# EEZ_DIB_AUX_PS_r2B2.net
KiCad netlist of a schematic drawn in EAGLE
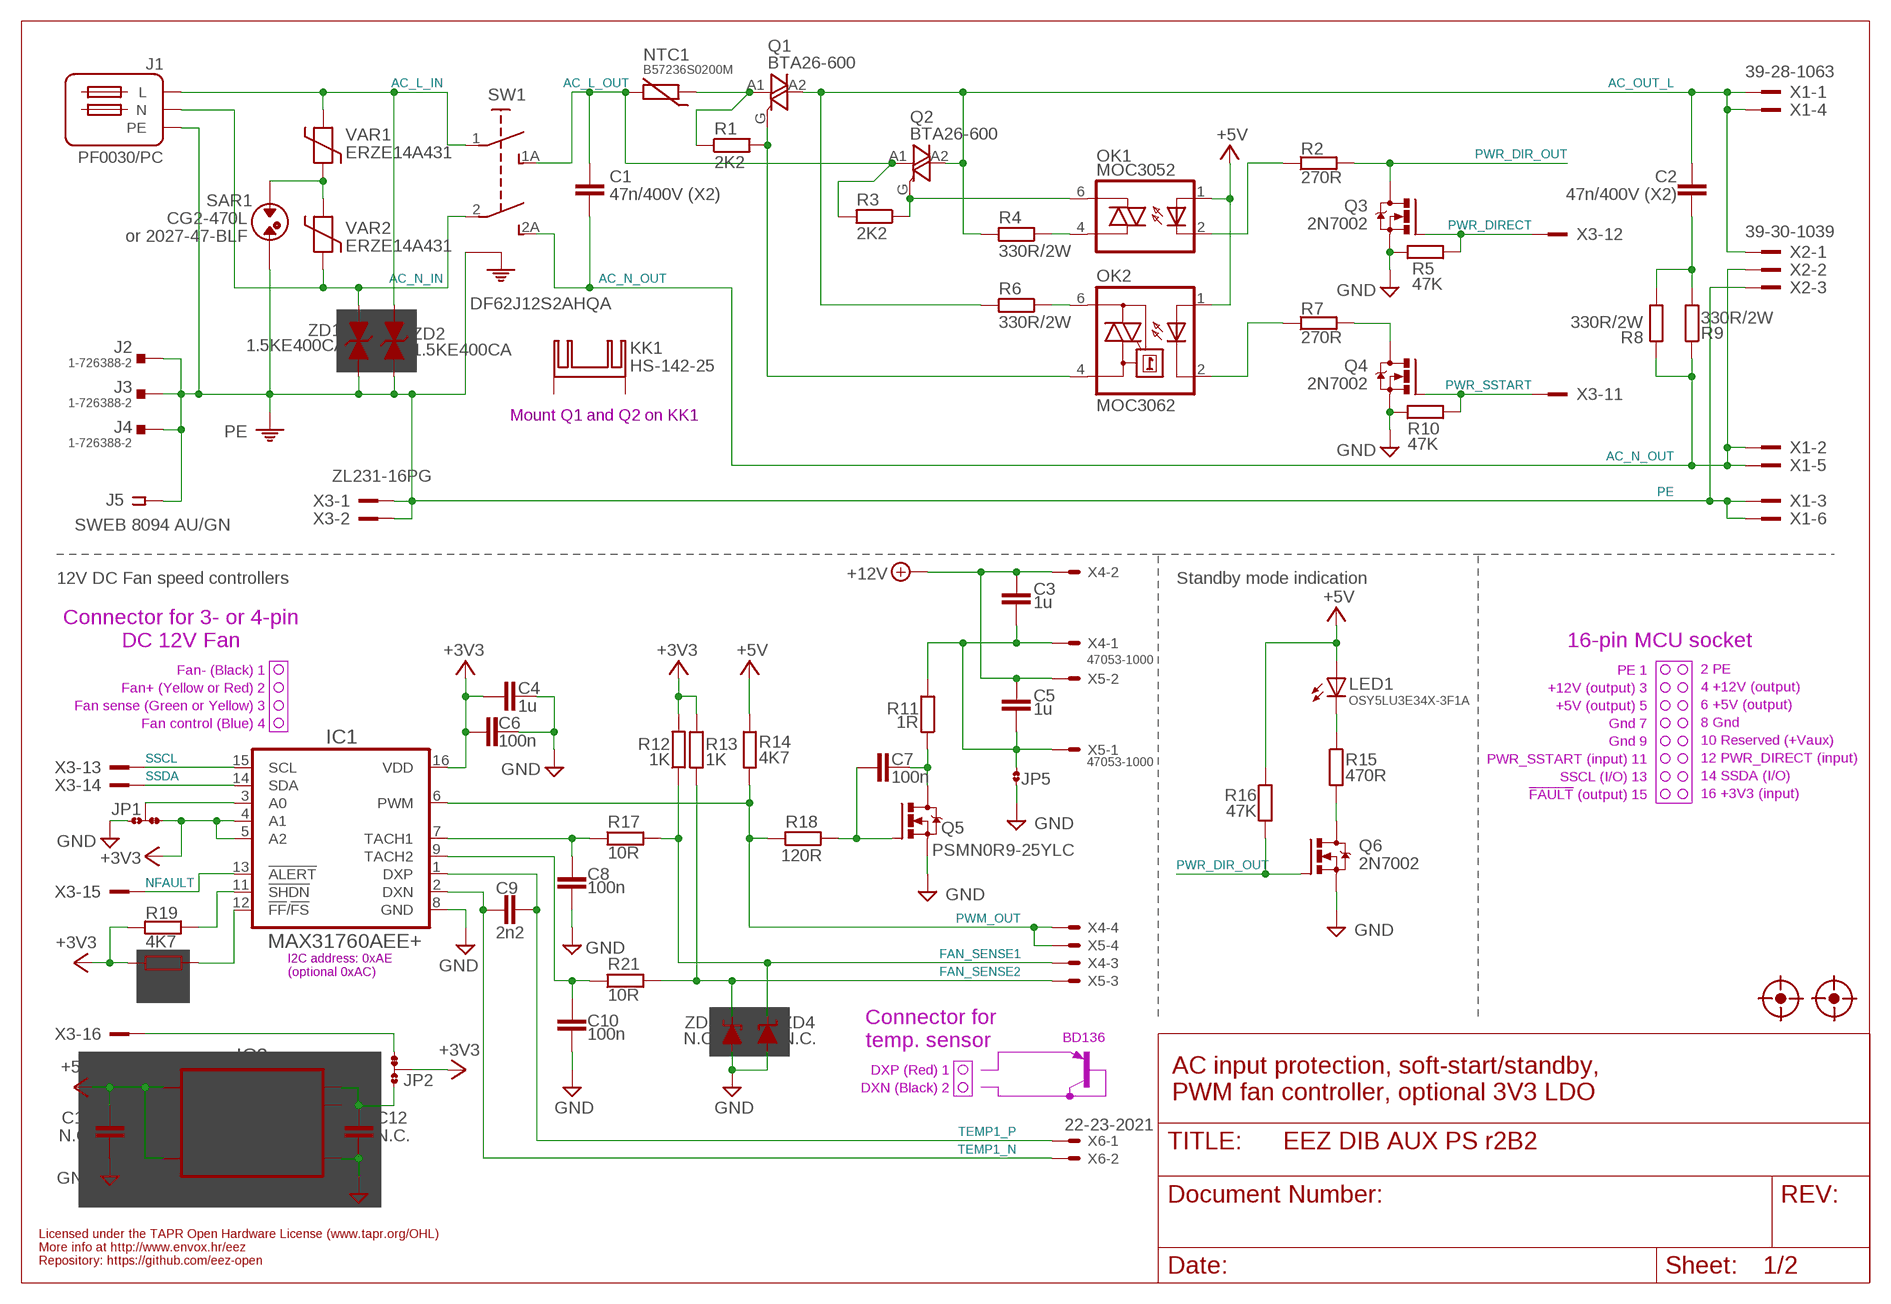
[diagram p0: schematic, sheet 1]
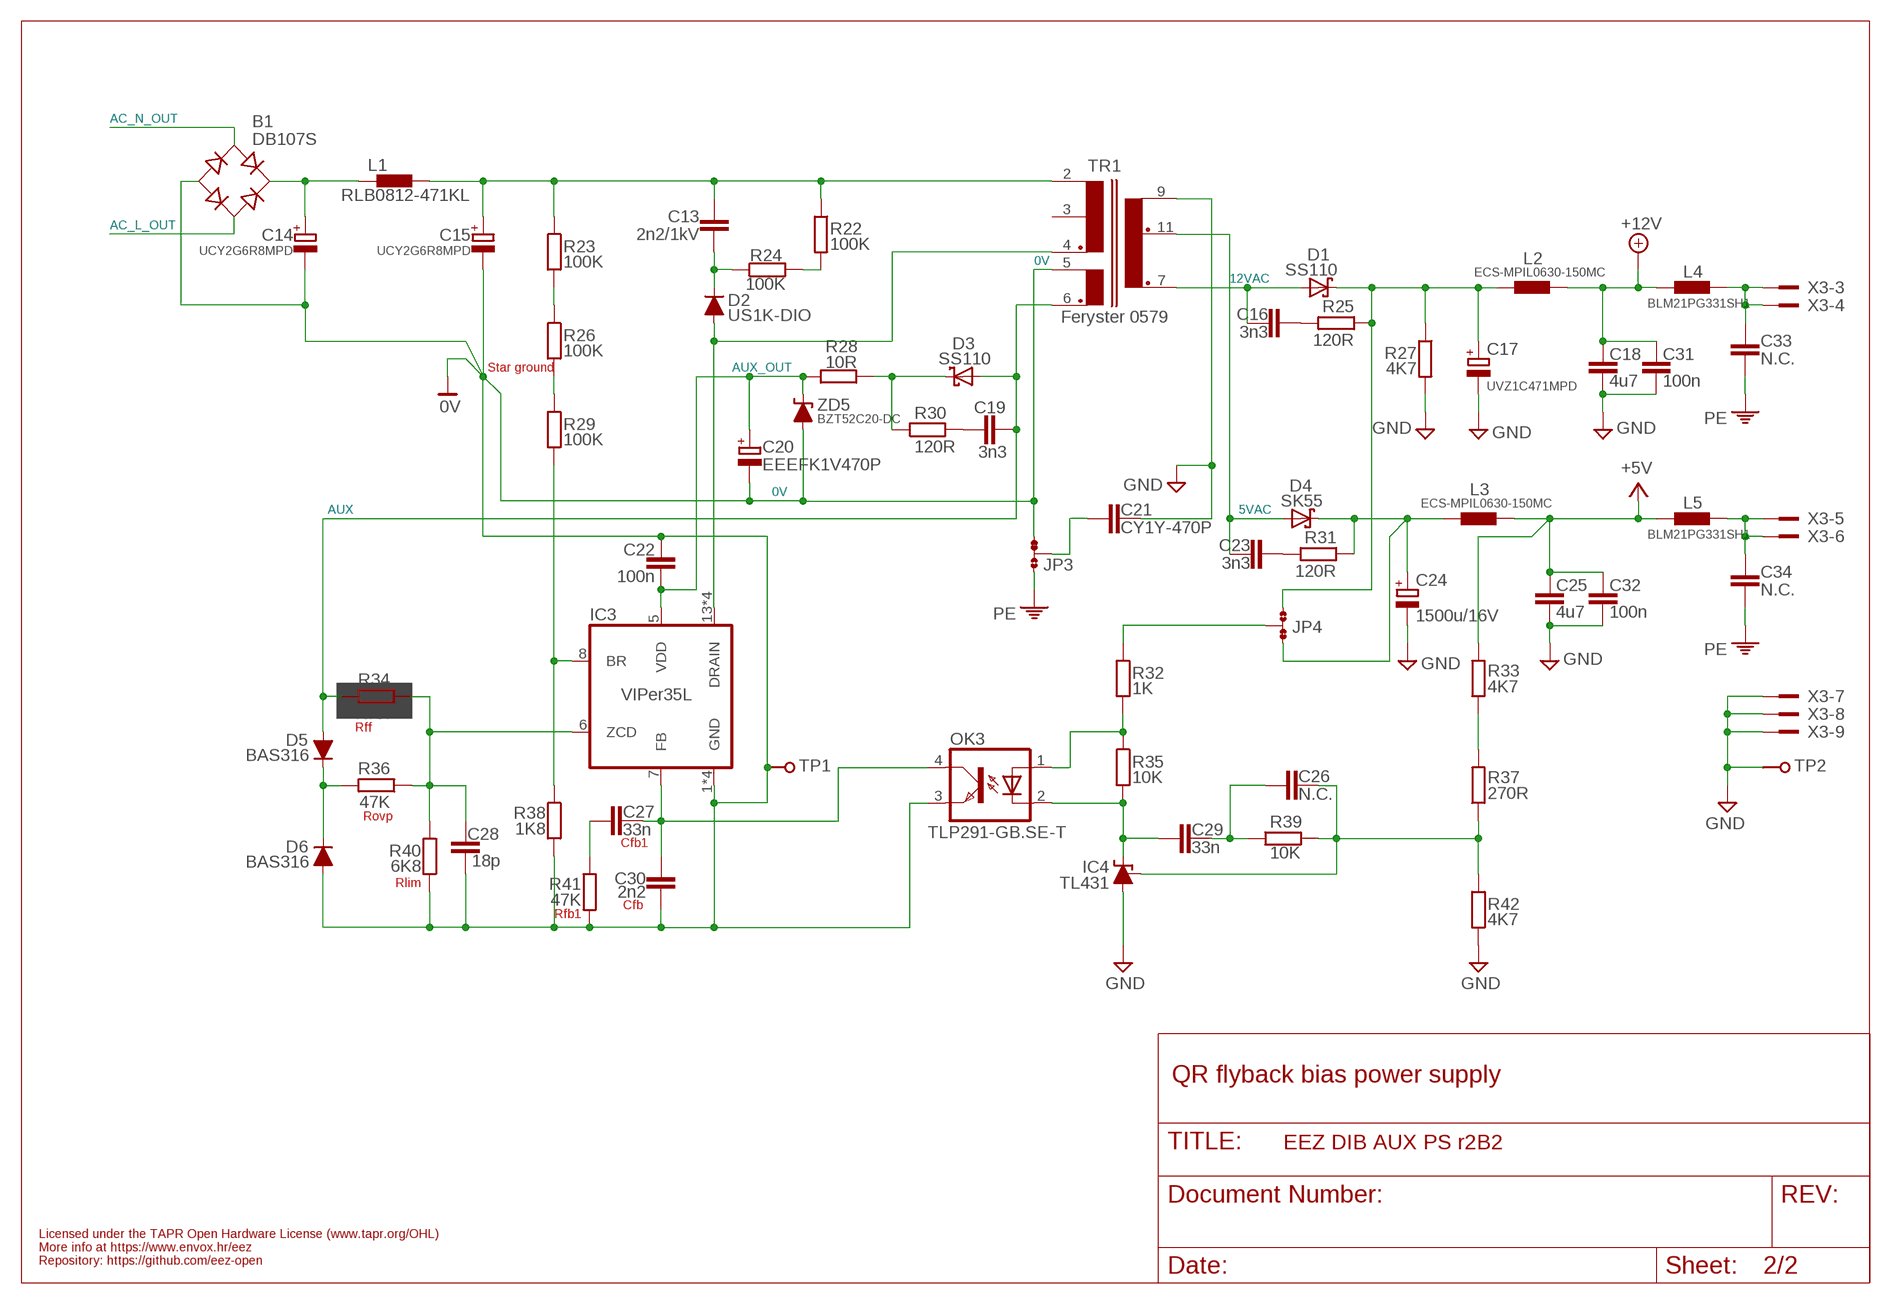
[diagram p1: schematic, sheet 2]

(export (version "E")
  (design (tool "Eeschema 10.0.6"))
  (components
    (comp (ref "C1")
      (value "47n/400V (X2)")
      (footprint "eagle-import:C102-054X133")
      (libsource (lib "eagle-import") (part "C-EU102-054X133"))
    )
    (comp (ref "C2")
      (value "47n/400V (X2)")
      (footprint "eagle-import:C102-054X133")
      (libsource (lib "eagle-import") (part "C-EU102-054X133"))
    )
    (comp (ref "C3")
      (value "1u")
      (footprint "eagle-import:C0805")
      (libsource (lib "eagle-import") (part "C-EUC0805"))
    )
    (comp (ref "C4")
      (value "1u")
      (footprint "eagle-import:C0805")
      (libsource (lib "eagle-import") (part "C-EUC0805"))
    )
    (comp (ref "C5")
      (value "1u")
      (footprint "eagle-import:C0805")
      (libsource (lib "eagle-import") (part "C-EUC0805"))
    )
    (comp (ref "C6")
      (value "100n")
      (footprint "eagle-import:C0603")
      (libsource (lib "eagle-import") (part "C-EUC0603"))
    )
    (comp (ref "C7")
      (value "100n")
      (footprint "eagle-import:C0805")
      (libsource (lib "eagle-import") (part "C-EUC0805"))
    )
    (comp (ref "C8")
      (value "100n")
      (footprint "eagle-import:C0603")
      (libsource (lib "eagle-import") (part "C-EUC0603"))
    )
    (comp (ref "C9")
      (value "2n2")
      (footprint "eagle-import:C0805")
      (libsource (lib "eagle-import") (part "C-EUC0805"))
    )
    (comp (ref "C10")
      (value "100n")
      (footprint "eagle-import:C0603")
      (libsource (lib "eagle-import") (part "C-EUC0603"))
    )
    (comp (ref "C11")
      (value "N.C.")
      (footprint "eagle-import:C0805")
      (libsource (lib "eagle-import") (part "C-EUC0805"))
    )
    (comp (ref "C12")
      (value "N.C.")
      (footprint "eagle-import:C0805")
      (libsource (lib "eagle-import") (part "C-EUC0805"))
    )
    (comp (ref "FM1")
      (value "FIDUCIAL")
      (footprint "eagle-import:FIDUCIAL")
      (libsource (lib "eagle-import") (part "FIDUCIAL"))
    )
    (comp (ref "FM2")
      (value "FIDUCIAL")
      (footprint "eagle-import:FIDUCIAL")
      (libsource (lib "eagle-import") (part "FIDUCIAL"))
    )
    (comp (ref "IC1")
      (value "MAX31760AEE+")
      (footprint "eagle-import:DBQ16")
      (libsource (lib "eagle-import") (part "MAX31760AEE+"))
    )
    (comp (ref "IC2")
      (value "LP2985")
      (footprint "eagle-import:SOT95P270X145-5N")
      (libsource (lib "eagle-import") (part "LP2985"))
    )
    (comp (ref "J1")
      (value "PF0030/PC")
      (footprint "eagle-import:PF0030_PC")
      (libsource (lib "eagle-import") (part "PF0030/PC"))
    )
    (comp (ref "J2")
      (value "1-726388-2")
      (footprint "eagle-import:PCB_TAB-4.8MM")
      (libsource (lib "eagle-import") (part "PCB_TAB4.8MM"))
    )
    (comp (ref "J3")
      (value "1-726388-2")
      (footprint "eagle-import:PCB_TAB-4.8MM")
      (libsource (lib "eagle-import") (part "PCB_TAB4.8MM"))
    )
    (comp (ref "J4")
      (value "1-726388-2")
      (footprint "eagle-import:PCB_TAB-4.8MM")
      (libsource (lib "eagle-import") (part "PCB_TAB4.8MM"))
    )
    (comp (ref "J5")
      (value "SWEB 8094 AU/GN")
      (footprint "eagle-import:S16N-PC")
      (libsource (lib "eagle-import") (part "BINDING_POSTCLIFF"))
    )
    (comp (ref "JP1")
      (value "JP3-CUT")
      (footprint "eagle-import:JP3-CUT")
      (libsource (lib "eagle-import") (part "JP3-CUT"))
    )
    (comp (ref "JP2")
      (value "JP3-CUT")
      (footprint "eagle-import:JP3-CUT")
      (libsource (lib "eagle-import") (part "JP3-CUT"))
    )
    (comp (ref "JP5")
      (value "JP2-CUT")
      (footprint "eagle-import:JP2-CUT")
      (libsource (lib "eagle-import") (part "JP2-CUT"))
    )
    (comp (ref "KK1")
      (value "HS-142-25")
      (footprint "eagle-import:SK129")
      (libsource (lib "eagle-import") (part "SK129-PAD"))
    )
    (comp (ref "LED1")
      (value "OSY5LU3E34X-3F1A")
      (footprint "eagle-import:OSG8")
      (libsource (lib "eagle-import") (part "LEDOSG8"))
    )
    (comp (ref "NTC1")
      (value "B57236S0200M")
      (footprint "eagle-import:NTC_11.5X6_RM5")
      (libsource (lib "eagle-import") (part "NTC11.5X6"))
    )
    (comp (ref "OK1")
      (value "MOC3052")
      (footprint "eagle-import:DIL6-SMD")
      (libsource (lib "eagle-import") (part "MOC305X"))
    )
    (comp (ref "OK2")
      (value "MOC3062")
      (footprint "eagle-import:DIL6-SMD")
      (fields
        (field (name "MF") "FAIRCHILD SEMICONDUCTOR")
        (field (name "MPN") "MOC3033S-M")
        (field (name "MF_1") "FAIRCHILD SEMICONDUCTOR")
        (field (name "MPN_1") "MOC3033S-M")
        (field (name "OC_FARNELL") "unknown")
        (field (name "OC_NEWARK") "05C2878")
      )
      (libsource (lib "eagle-import") (part "MOC30S33"))
    )
    (comp (ref "Q1")
      (value "BTA26-600")
      (footprint "eagle-import:TOP3S-1")
      (libsource (lib "eagle-import") (part "BTA26-V"))
    )
    (comp (ref "Q2")
      (value "BTA26-600")
      (footprint "eagle-import:TOP3S-1")
      (libsource (lib "eagle-import") (part "BTA26-V"))
    )
    (comp (ref "Q3")
      (value "2N7002")
      (footprint "eagle-import:SOT103P240X110-3N")
      (fields (field (name "MPN") "2N7002-7-F"))
      (libsource (lib "eagle-import") (part "2N7002"))
    )
    (comp (ref "Q4")
      (value "2N7002")
      (footprint "eagle-import:SOT103P240X110-3N")
      (fields (field (name "MPN") "2N7002-7-F"))
      (libsource (lib "eagle-import") (part "2N7002"))
    )
    (comp (ref "Q5")
      (value "PSMN0R9-25YLC")
      (footprint "eagle-import:SOT669")
      (libsource (lib "eagle-import") (part "N-MOSFETLFPAK"))
    )
    (comp (ref "Q6")
      (value "2N7002")
      (footprint "eagle-import:SOT103P240X110-3N")
      (fields
        (field (name "MPN") "2N7002-7-F")
        (field (name "MPN_1") "2N7002-7-F")
        (field (name "OC_FARNELL") "1713823")
        (field (name "OC_NEWARK") "25R5679")
        (field (name "PACKAGE") "SOT-23-3")
        (field (name "SUPPLIER") "DIODES INC.")
      )
      (libsource (lib "eagle-import") (part "2N7002"))
    )
    (comp (ref "R1")
      (value "2K2")
      (footprint "eagle-import:R0805")
      (libsource (lib "eagle-import") (part "R-EU_R0805"))
    )
    (comp (ref "R2")
      (value "270R")
      (footprint "eagle-import:R0805")
      (libsource (lib "eagle-import") (part "R-EU_R0805"))
    )
    (comp (ref "R3")
      (value "2K2")
      (footprint "eagle-import:R0805")
      (libsource (lib "eagle-import") (part "R-EU_R0805"))
    )
    (comp (ref "R4")
      (value "330R/2W")
      (footprint "eagle-import:R2512")
      (libsource (lib "eagle-import") (part "R-EU_R2512"))
    )
    (comp (ref "R5")
      (value "47K")
      (footprint "eagle-import:R0805")
      (libsource (lib "eagle-import") (part "R-EU_R0805"))
    )
    (comp (ref "R6")
      (value "330R/2W")
      (footprint "eagle-import:R2512")
      (libsource (lib "eagle-import") (part "R-EU_R2512"))
    )
    (comp (ref "R7")
      (value "270R")
      (footprint "eagle-import:R0805")
      (libsource (lib "eagle-import") (part "R-EU_R0805"))
    )
    (comp (ref "R8")
      (value "330R/2W")
      (footprint "eagle-import:R2512")
      (libsource (lib "eagle-import") (part "R-EU_R2512"))
    )
    (comp (ref "R9")
      (value "330R/2W")
      (footprint "eagle-import:R2512")
      (libsource (lib "eagle-import") (part "R-EU_R2512"))
    )
    (comp (ref "R10")
      (value "47K")
      (footprint "eagle-import:R0805")
      (libsource (lib "eagle-import") (part "R-EU_R0805"))
    )
    (comp (ref "R11")
      (value "1R")
      (footprint "eagle-import:R0805")
      (libsource (lib "eagle-import") (part "R-EU_R0805"))
    )
    (comp (ref "R12")
      (value "1K")
      (footprint "eagle-import:R0805")
      (libsource (lib "eagle-import") (part "R-EU_R0805"))
    )
    (comp (ref "R13")
      (value "1K")
      (footprint "eagle-import:R0805")
      (libsource (lib "eagle-import") (part "R-EU_R0805"))
    )
    (comp (ref "R14")
      (value "4K7")
      (footprint "eagle-import:R0805")
      (libsource (lib "eagle-import") (part "R-EU_R0805"))
    )
    (comp (ref "R15")
      (value "470R")
      (footprint "eagle-import:R0805")
      (libsource (lib "eagle-import") (part "R-EU_R0805"))
    )
    (comp (ref "R16")
      (value "47K")
      (footprint "eagle-import:R0805")
      (libsource (lib "eagle-import") (part "R-EU_R0805"))
    )
    (comp (ref "R17")
      (value "10R")
      (footprint "eagle-import:R0805")
      (libsource (lib "eagle-import") (part "R-EU_R0805"))
    )
    (comp (ref "R18")
      (value "120R")
      (footprint "eagle-import:R0805")
      (libsource (lib "eagle-import") (part "R-EU_R0805"))
    )
    (comp (ref "R19")
      (value "4K7")
      (footprint "eagle-import:R0805")
      (libsource (lib "eagle-import") (part "R-EU_R0805"))
    )
    (comp (ref "R20")
      (value "N.C.")
      (footprint "eagle-import:R0805")
      (libsource (lib "eagle-import") (part "R-EU_R0805"))
    )
    (comp (ref "R21")
      (value "10R")
      (footprint "eagle-import:R0805")
      (libsource (lib "eagle-import") (part "R-EU_R0805"))
    )
    (comp (ref "SAR1")
      (value "CG2-470L")
      (footprint "eagle-import:SAR")
      (libsource (lib "eagle-import") (part "SAR"))
    )
    (comp (ref "SW1")
      (value "DF62J12S2AHQA")
      (footprint "eagle-import:DF62J12S2")
      (libsource (lib "eagle-import") (part "DF62J12S2AHQA"))
    )
    (comp (ref "VAR1")
      (value "ERZE14A431")
      (footprint "eagle-import:VARISTOR_13MM")
      (libsource (lib "eagle-import") (part "VARISTOR-13"))
    )
    (comp (ref "VAR2")
      (value "ERZE14A431")
      (footprint "eagle-import:VARISTOR_13MM")
      (libsource (lib "eagle-import") (part "VARISTOR-13"))
    )
    (comp (ref "X1")
      (value "39-28-1063")
      (footprint "eagle-import:MINIFIT_5566-06A_CRE")
      (libsource (lib "eagle-import") (part "MINIFIT_5566-06A-CRE"))
    )
    (comp (ref "X2")
      (value "39-30-1039")
      (footprint "eagle-import:MINIFIT_39301039_CRE")
      (libsource (lib "eagle-import") (part "MINIFIT_39301039-CREEPAGE"))
    )
    (comp (ref "X3")
      (value "ZL231-16PG")
      (footprint "eagle-import:IDC-16PIN")
      (libsource (lib "eagle-import") (part "IDC-16PIN"))
    )
    (comp (ref "X4")
      (value "47053-1000")
      (footprint "eagle-import:47053-1000")
      (libsource (lib "eagle-import") (part "47053-1000"))
    )
    (comp (ref "X5")
      (value "47053-1000")
      (footprint "eagle-import:47053-1000")
      (libsource (lib "eagle-import") (part "47053-1000"))
    )
    (comp (ref "X6")
      (value "22-23-2021")
      (footprint "eagle-import:22-23-2021")
      (fields (field (name "MF") "MOLEX"))
      (libsource (lib "eagle-import") (part "22-23-2021"))
    )
    (comp (ref "ZD1")
      (value "1.5KE400CA")
      (footprint "eagle-import:DO201-BIDIR")
      (libsource (lib "eagle-import") (part "1.5KE-BIDIR"))
    )
    (comp (ref "ZD2")
      (value "1.5KE400CA")
      (footprint "eagle-import:DO201-BIDIR")
      (libsource (lib "eagle-import") (part "1.5KE-BIDIR"))
    )
    (comp (ref "ZD3")
      (value "N.C.")
      (footprint "eagle-import:SOD123")
      (libsource (lib "eagle-import") (part "ZENER-DIODESOD123"))
    )
    (comp (ref "ZD4")
      (value "N.C.")
      (footprint "eagle-import:SOD123")
      (libsource (lib "eagle-import") (part "ZENER-DIODESOD123"))
    )
    (comp (ref "B1")
      (value "DB107S")
      (footprint "eagle-import:DBS")
      (libsource (lib "eagle-import") (part "DB?GS107"))
    )
    (comp (ref "C13")
      (value "2n2/1kV")
      (footprint "eagle-import:C1210")
      (libsource (lib "eagle-import") (part "C-EUC1210"))
    )
    (comp (ref "C14")
      (value "UCY2G6R8MPD")
      (footprint "eagle-import:ECAP5_10.5")
      (libsource (lib "eagle-import") (part "ECAP5G_10.5MM"))
    )
    (comp (ref "C15")
      (value "UCY2G6R8MPD")
      (footprint "eagle-import:ECAP5_10.5")
      (libsource (lib "eagle-import") (part "ECAP5G_10.5MM"))
    )
    (comp (ref "C16")
      (value "3n3")
      (footprint "eagle-import:C0805")
      (libsource (lib "eagle-import") (part "C-EUC0805"))
    )
    (comp (ref "C17")
      (value "UVZ1C471MPD")
      (footprint "eagle-import:ECAP5_10.5")
      (libsource (lib "eagle-import") (part "ECAP5G_10.5MM"))
    )
    (comp (ref "C18")
      (value "4u7")
      (footprint "eagle-import:C1210")
      (libsource (lib "eagle-import") (part "C-EUC1210"))
    )
    (comp (ref "C19")
      (value "3n3")
      (footprint "eagle-import:C0805")
      (libsource (lib "eagle-import") (part "C-EUC0805"))
    )
    (comp (ref "C20")
      (value "EEEFK1V470P")
      (footprint "eagle-import:CAPAE660X610N")
      (libsource (lib "eagle-import") (part "ECAPPANASONIC_H"))
    )
    (comp (ref "C21")
      (value "CY1Y-470P")
      (footprint "eagle-import:CY075-032X103")
      (libsource (lib "eagle-import") (part "C-EUCY"))
    )
    (comp (ref "C22")
      (value "100n")
      (footprint "eagle-import:C0603")
      (libsource (lib "eagle-import") (part "C-EUC0603"))
    )
    (comp (ref "C23")
      (value "3n3")
      (footprint "eagle-import:C0805")
      (libsource (lib "eagle-import") (part "C-EUC0805"))
    )
    (comp (ref "C24")
      (value "1500u/16V")
      (footprint "eagle-import:ECAP5_13")
      (libsource (lib "eagle-import") (part "ECAP5G_13MM"))
    )
    (comp (ref "C25")
      (value "4u7")
      (footprint "eagle-import:C1210")
      (libsource (lib "eagle-import") (part "C-EUC1210"))
    )
    (comp (ref "C26")
      (value "N.C.")
      (footprint "eagle-import:C0805")
      (libsource (lib "eagle-import") (part "C-EUC0805"))
    )
    (comp (ref "C27")
      (value "33n")
      (footprint "eagle-import:C0805")
      (libsource (lib "eagle-import") (part "C-EUC0805"))
    )
    (comp (ref "C28")
      (value "18p")
      (footprint "eagle-import:C0603")
      (libsource (lib "eagle-import") (part "C-EUC0603"))
    )
    (comp (ref "C29")
      (value "33n")
      (footprint "eagle-import:C0805")
      (libsource (lib "eagle-import") (part "C-EUC0805"))
    )
    (comp (ref "C30")
      (value "2n2")
      (footprint "eagle-import:C0805")
      (libsource (lib "eagle-import") (part "C-EUC0805"))
    )
    (comp (ref "C31")
      (value "100n")
      (footprint "eagle-import:C0603")
      (libsource (lib "eagle-import") (part "C-EUC0603"))
    )
    (comp (ref "C32")
      (value "100n")
      (footprint "eagle-import:C0603")
      (libsource (lib "eagle-import") (part "C-EUC0603"))
    )
    (comp (ref "C33")
      (value "N.C.")
      (footprint "eagle-import:C1206")
      (libsource (lib "eagle-import") (part "C-EUC1206"))
    )
    (comp (ref "C34")
      (value "N.C.")
      (footprint "eagle-import:C1206")
      (libsource (lib "eagle-import") (part "C-EUC1206"))
    )
    (comp (ref "D1")
      (value "SS110")
      (footprint "eagle-import:SMB")
      (libsource (lib "eagle-import") (part "SCHOTTKYSMB"))
    )
    (comp (ref "D2")
      (value "US1K-DIO")
      (footprint "eagle-import:DO214AA")
      (libsource (lib "eagle-import") (part "DIODEDO214AA"))
    )
    (comp (ref "D3")
      (value "SS110")
      (footprint "eagle-import:SMB")
      (libsource (lib "eagle-import") (part "SCHOTTKYSMB"))
    )
    (comp (ref "D4")
      (value "SK55")
      (footprint "eagle-import:SMB")
      (libsource (lib "eagle-import") (part "SCHOTTKYSMB"))
    )
    (comp (ref "D5")
      (value "BAS316")
      (footprint "eagle-import:SOD323-R")
      (libsource (lib "eagle-import") (part "DIODESOD323R"))
    )
    (comp (ref "D6")
      (value "BAS316")
      (footprint "eagle-import:SOD323-R")
      (libsource (lib "eagle-import") (part "DIODESOD323R"))
    )
    (comp (ref "IC3")
      (value "VIPer35L")
      (footprint "eagle-import:SOIC-16")
      (libsource (lib "eagle-import") (part "VIPER35"))
    )
    (comp (ref "IC4")
      (value "TL431")
      (footprint "eagle-import:SOT103P240X110-3N")
      (libsource (lib "eagle-import") (part "TL431"))
    )
    (comp (ref "JP3")
      (value "JP3-CUT")
      (footprint "eagle-import:JP3-CUT")
      (libsource (lib "eagle-import") (part "JP3-CUT"))
    )
    (comp (ref "JP4")
      (value "JP3-CUT")
      (footprint "eagle-import:JP3-CUT")
      (libsource (lib "eagle-import") (part "JP3-CUT"))
    )
    (comp (ref "L1")
      (value "RLB0812-471KL")
      (footprint "eagle-import:FERSYTER_DSZ6")
      (libsource (lib "eagle-import") (part "FERYSTER_DSZ6"))
    )
    (comp (ref "L2")
      (value "ECS-MPIL0630-150MC")
      (footprint "eagle-import:DE0704")
      (libsource (lib "eagle-import") (part "DE0704"))
    )
    (comp (ref "L3")
      (value "ECS-MPIL0630-150MC")
      (footprint "eagle-import:DE0704")
      (libsource (lib "eagle-import") (part "DE0704"))
    )
    (comp (ref "L4")
      (value "BLM21PG331SH1")
      (footprint "eagle-import:0805")
      (libsource (lib "eagle-import") (part "L-EU0805"))
    )
    (comp (ref "L5")
      (value "BLM21PG331SH1")
      (footprint "eagle-import:0805")
      (libsource (lib "eagle-import") (part "L-EU0805"))
    )
    (comp (ref "OK3")
      (value "TLP291-GB.SE-T")
      (footprint "eagle-import:SO4")
      (libsource (lib "eagle-import") (part "TLP291"))
    )
    (comp (ref "R22")
      (value "100K")
      (footprint "eagle-import:R1206")
      (libsource (lib "eagle-import") (part "R-EU_R1206"))
    )
    (comp (ref "R23")
      (value "100K")
      (footprint "eagle-import:R1206")
      (libsource (lib "eagle-import") (part "R-EU_R1206"))
    )
    (comp (ref "R24")
      (value "100K")
      (footprint "eagle-import:R1206")
      (libsource (lib "eagle-import") (part "R-EU_R1206"))
    )
    (comp (ref "R25")
      (value "120R")
      (footprint "eagle-import:R0805")
      (libsource (lib "eagle-import") (part "R-EU_R0805"))
    )
    (comp (ref "R26")
      (value "100K")
      (footprint "eagle-import:R1206")
      (libsource (lib "eagle-import") (part "R-EU_R1206"))
    )
    (comp (ref "R27")
      (value "4K7")
      (footprint "eagle-import:R0805")
      (libsource (lib "eagle-import") (part "R-EU_R0805"))
    )
    (comp (ref "R28")
      (value "10R")
      (footprint "eagle-import:R0805")
      (libsource (lib "eagle-import") (part "R-EU_R0805"))
    )
    (comp (ref "R29")
      (value "100K")
      (footprint "eagle-import:R1206")
      (libsource (lib "eagle-import") (part "R-EU_R1206"))
    )
    (comp (ref "R30")
      (value "120R")
      (footprint "eagle-import:R0805")
      (libsource (lib "eagle-import") (part "R-EU_R0805"))
    )
    (comp (ref "R31")
      (value "120R")
      (footprint "eagle-import:R0805")
      (libsource (lib "eagle-import") (part "R-EU_R0805"))
    )
    (comp (ref "R32")
      (value "1K")
      (footprint "eagle-import:R0805")
      (libsource (lib "eagle-import") (part "R-EU_R0805"))
    )
    (comp (ref "R33")
      (value "4K7")
      (footprint "eagle-import:R0805")
      (libsource (lib "eagle-import") (part "R-EU_R0805"))
    )
    (comp (ref "R34")
      (value "N.C.")
      (footprint "eagle-import:R0805")
      (libsource (lib "eagle-import") (part "R-EU_R0805"))
    )
    (comp (ref "R35")
      (value "10K")
      (footprint "eagle-import:R0805")
      (libsource (lib "eagle-import") (part "R-EU_R0805"))
    )
    (comp (ref "R36")
      (value "47K")
      (footprint "eagle-import:R0805")
      (libsource (lib "eagle-import") (part "R-EU_R0805"))
    )
    (comp (ref "R37")
      (value "270R")
      (footprint "eagle-import:R0805")
      (libsource (lib "eagle-import") (part "R-EU_R0805"))
    )
    (comp (ref "R38")
      (value "1K8")
      (footprint "eagle-import:R0805")
      (libsource (lib "eagle-import") (part "R-EU_R0805"))
    )
    (comp (ref "R39")
      (value "10K")
      (footprint "eagle-import:R0805")
      (libsource (lib "eagle-import") (part "R-EU_R0805"))
    )
    (comp (ref "R40")
      (value "6K8")
      (footprint "eagle-import:R0805")
      (libsource (lib "eagle-import") (part "R-EU_R0805"))
    )
    (comp (ref "R41")
      (value "47K")
      (footprint "eagle-import:R0805")
      (libsource (lib "eagle-import") (part "R-EU_R0805"))
    )
    (comp (ref "R42")
      (value "4K7")
      (footprint "eagle-import:R0805")
      (libsource (lib "eagle-import") (part "R-EU_R0805"))
    )
    (comp (ref "TP1")
      (value "PCB_TEST_TABSHIELD")
      (footprint "eagle-import:PCB_SHIELD_TAB")
      (libsource (lib "eagle-import") (part "PCB_TEST_TABSHIELD"))
    )
    (comp (ref "TP2")
      (value "PCB_TEST_TABSHIELD")
      (footprint "eagle-import:PCB_SHIELD_TAB")
      (libsource (lib "eagle-import") (part "PCB_TEST_TABSHIELD"))
    )
    (comp (ref "TR1")
      (value "Feryster 0579")
      (footprint "eagle-import:FERYSTER_0579")
      (libsource (lib "eagle-import") (part "FERYSTER_0579"))
    )
    (comp (ref "ZD5")
      (value "BZT52C20-DC")
      (footprint "eagle-import:SOD123")
      (libsource (lib "eagle-import") (part "ZENER-DIODESOD123"))
    )
  )
  (nets
    (net (code "1") (name "+3V3") (class "Default")
      (node (ref "C4") (pin "2") (pinfunction "2_2") (pintype "passive"))
      (node (ref "C6") (pin "2") (pinfunction "2_2") (pintype "passive"))
      (node (ref "IC1") (pin "16") (pinfunction "VDD_16") (pintype "power_in"))
      (node (ref "IC1") (pin "4") (pinfunction "A1_4") (pintype "input"))
      (node (ref "IC1") (pin "5") (pinfunction "A2_5") (pintype "input"))
      (node (ref "JP1") (pin "NC") (pinfunction "NC_NC") (pintype "passive"))
      (node (ref "JP2") (pin "COM") (pinfunction "COM_COM") (pintype "passive"))
      (node (ref "R12") (pin "2") (pinfunction "2_2") (pintype "passive"))
      (node (ref "R13") (pin "2") (pinfunction "2_2") (pintype "passive"))
      (node (ref "R19") (pin "2") (pinfunction "2_2") (pintype "passive"))
      (node (ref "R20") (pin "2") (pinfunction "2_2") (pintype "passive"))
    )
    (net (code "2") (name "+5V") (class "Default")
      (node (ref "C11") (pin "1") (pinfunction "1_1") (pintype "passive"))
      (node (ref "C25") (pin "1") (pinfunction "1_1") (pintype "passive"))
      (node (ref "C32") (pin "1") (pinfunction "1_1") (pintype "passive"))
      (node (ref "IC2") (pin "1") (pinfunction "IN_1") (pintype "input"))
      (node (ref "IC2") (pin "3") (pinfunction "ON/~{OFF}_3") (pintype "input"))
      (node (ref "L3") (pin "2") (pinfunction "2_2") (pintype "passive"))
      (node (ref "L5") (pin "1") (pinfunction "1_1") (pintype "passive"))
      (node (ref "LED1") (pin "A") (pinfunction "A_A") (pintype "passive"))
      (node (ref "OK1") (pin "1") (pinfunction "A_1") (pintype "passive"))
      (node (ref "OK2") (pin "1") (pinfunction "A_1") (pintype "passive"))
      (node (ref "R14") (pin "1") (pinfunction "1_1") (pintype "passive"))
      (node (ref "R16") (pin "1") (pinfunction "1_1") (pintype "passive"))
      (node (ref "R33") (pin "2") (pinfunction "2_2") (pintype "passive"))
    )
    (net (code "3") (name "+12V") (class "Default")
      (node (ref "C18") (pin "1") (pinfunction "1_1") (pintype "passive"))
      (node (ref "C3") (pin "1") (pinfunction "1_1") (pintype "passive"))
      (node (ref "C31") (pin "1") (pinfunction "1_1") (pintype "passive"))
      (node (ref "C5") (pin "1") (pinfunction "1_1") (pintype "passive"))
      (node (ref "L2") (pin "2") (pinfunction "2_2") (pintype "passive"))
      (node (ref "L4") (pin "1") (pinfunction "1_1") (pintype "passive"))
      (node (ref "X4") (pin "2") (pinfunction "S_2") (pintype "passive"))
      (node (ref "X5") (pin "2") (pinfunction "S_2") (pintype "passive"))
    )
    (net (code "4") (name "0V") (class "Default")
      (node (ref "B1") (pin "-") (pinfunction "-_-") (pintype "passive"))
      (node (ref "C14") (pin "-") (pinfunction "-_-") (pintype "passive"))
      (node (ref "C15") (pin "-") (pinfunction "-_-") (pintype "passive"))
      (node (ref "C20") (pin "2") (pinfunction "-_2") (pintype "passive"))
      (node (ref "C22") (pin "1") (pinfunction "1_1") (pintype "passive"))
      (node (ref "C28") (pin "2") (pinfunction "2_2") (pintype "passive"))
      (node (ref "C30") (pin "2") (pinfunction "2_2") (pintype "passive"))
      (node (ref "D6") (pin "A") (pinfunction "A_A") (pintype "passive"))
      (node (ref "IC3") (pin "1") (pinfunction "GND_1") (pintype "passive"))
      (node (ref "IC3") (pin "2") (pinfunction "GND_2") (pintype "passive"))
      (node (ref "IC3") (pin "3") (pinfunction "GND_3") (pintype "passive"))
      (node (ref "IC3") (pin "4") (pinfunction "GND_4") (pintype "passive"))
      (node (ref "JP3") (pin "NC") (pinfunction "NC_NC") (pintype "passive"))
      (node (ref "OK3") (pin "3") (pinfunction "EMIT_3") (pintype "passive"))
      (node (ref "R38") (pin "2") (pinfunction "2_2") (pintype "passive"))
      (node (ref "R40") (pin "1") (pinfunction "1_1") (pintype "passive"))
      (node (ref "R41") (pin "2") (pinfunction "2_2") (pintype "passive"))
      (node (ref "TP1") (pin "1") (pinfunction "P$1_1") (pintype "bidirectional"))
      (node (ref "TR1") (pin "5") (pinfunction "AUX_5") (pintype "passive"))
      (node (ref "ZD5") (pin "A") (pinfunction "A_A") (pintype "passive"))
    )
    (net (code "5") (name "5VAC") (class "Default")
      (node (ref "C23") (pin "2") (pinfunction "2_2") (pintype "passive"))
      (node (ref "D4") (pin "A") (pinfunction "A_A") (pintype "passive"))
      (node (ref "TR1") (pin "11") (pinfunction "S1_DOT_11") (pintype "passive"))
    )
    (net (code "6") (name "12VAC") (class "Default")
      (node (ref "C16") (pin "2") (pinfunction "2_2") (pintype "passive"))
      (node (ref "D1") (pin "A") (pinfunction "A_A") (pintype "passive"))
      (node (ref "TR1") (pin "7") (pinfunction "S2_DOT_7") (pintype "passive"))
    )
    (net (code "7") (name "AC_L_IN") (class "Default")
      (node (ref "J1") (pin "L") (pinfunction "L_L") (pintype "bidirectional"))
      (node (ref "SW1") (pin "1") (pinfunction "P_1") (pintype "passive"))
      (node (ref "VAR1") (pin "2") (pinfunction "P$2_2") (pintype "bidirectional"))
      (node (ref "ZD2") (pin "A") (pinfunction "2_A") (pintype "passive"))
    )
    (net (code "8") (name "AC_L_OUT") (class "Default")
      (node (ref "B1") (pin "AC2") (pinfunction "AC2_AC2") (pintype "passive"))
      (node (ref "C1") (pin "1") (pinfunction "1_1") (pintype "passive"))
      (node (ref "NTC1") (pin "1") (pinfunction "P$1_1") (pintype "bidirectional"))
      (node (ref "Q2") (pin "A1") (pinfunction "A1_A1") (pintype "passive"))
      (node (ref "R3") (pin "2") (pinfunction "2_2") (pintype "passive"))
      (node (ref "SW1") (pin "1A") (pinfunction "S_1A") (pintype "passive"))
    )
    (net (code "9") (name "AC_N_IN") (class "Default")
      (node (ref "J1") (pin "N") (pinfunction "N_N") (pintype "bidirectional"))
      (node (ref "SW1") (pin "2") (pinfunction "P1_2") (pintype "passive"))
      (node (ref "VAR2") (pin "1") (pinfunction "P$1_1") (pintype "bidirectional"))
      (node (ref "ZD1") (pin "A") (pinfunction "2_A") (pintype "passive"))
    )
    (net (code "10") (name "AC_N_OUT") (class "Default")
      (node (ref "B1") (pin "AC1") (pinfunction "AC1_AC1") (pintype "passive"))
      (node (ref "C1") (pin "2") (pinfunction "2_2") (pintype "passive"))
      (node (ref "R8") (pin "1") (pinfunction "1_1") (pintype "passive"))
      (node (ref "R9") (pin "1") (pinfunction "1_1") (pintype "passive"))
      (node (ref "SW1") (pin "2A") (pinfunction "S1_2A") (pintype "passive"))
      (node (ref "X1") (pin "2") (pinfunction "1_2") (pintype "passive"))
      (node (ref "X1") (pin "5") (pinfunction "1_5") (pintype "passive"))
      (node (ref "X2") (pin "2") (pinfunction "1_2") (pintype "passive"))
    )
    (net (code "11") (name "AC_OUT_L") (class "Default")
      (node (ref "C2") (pin "1") (pinfunction "1_1") (pintype "passive"))
      (node (ref "Q1") (pin "A2") (pinfunction "A2_A2") (pintype "passive"))
      (node (ref "Q2") (pin "A2") (pinfunction "A2_A2") (pintype "passive"))
      (node (ref "R4") (pin "2") (pinfunction "2_2") (pintype "passive"))
      (node (ref "R6") (pin "2") (pinfunction "2_2") (pintype "passive"))
      (node (ref "X1") (pin "1") (pinfunction "1_1") (pintype "passive"))
      (node (ref "X1") (pin "4") (pinfunction "1_4") (pintype "passive"))
      (node (ref "X2") (pin "1") (pinfunction "1_1") (pintype "passive"))
    )
    (net (code "12") (name "AUX") (class "Default")
      (node (ref "C19") (pin "2") (pinfunction "2_2") (pintype "passive"))
      (node (ref "D3") (pin "A") (pinfunction "A_A") (pintype "passive"))
      (node (ref "D5") (pin "A") (pinfunction "A_A") (pintype "passive"))
      (node (ref "R34") (pin "2") (pinfunction "2_2") (pintype "passive"))
      (node (ref "TR1") (pin "6") (pinfunction "AUX_DOT_6") (pintype "passive"))
    )
    (net (code "13") (name "AUX_OUT") (class "Default")
      (node (ref "C20") (pin "1") (pinfunction "+_1") (pintype "passive"))
      (node (ref "C22") (pin "2") (pinfunction "2_2") (pintype "passive"))
      (node (ref "IC3") (pin "5") (pinfunction "VDD_5") (pintype "power_in"))
      (node (ref "R28") (pin "2") (pinfunction "2_2") (pintype "passive"))
      (node (ref "ZD5") (pin "C") (pinfunction "C_C") (pintype "passive"))
    )
    (net (code "14") (name "FAN_SENSE1") (class "Default")
      (node (ref "R12") (pin "1") (pinfunction "1_1") (pintype "passive"))
      (node (ref "R17") (pin "2") (pinfunction "2_2") (pintype "passive"))
      (node (ref "X4") (pin "3") (pinfunction "S_3") (pintype "passive"))
      (node (ref "ZD4") (pin "C") (pinfunction "C_C") (pintype "passive"))
    )
    (net (code "15") (name "FAN_SENSE2") (class "Default")
      (node (ref "R13") (pin "1") (pinfunction "1_1") (pintype "passive"))
      (node (ref "R21") (pin "2") (pinfunction "2_2") (pintype "passive"))
      (node (ref "X5") (pin "3") (pinfunction "S_3") (pintype "passive"))
      (node (ref "ZD3") (pin "C") (pinfunction "C_C") (pintype "passive"))
    )
    (net (code "16") (name "GND") (class "Default")
      (node (ref "C10") (pin "2") (pinfunction "2_2") (pintype "passive"))
      (node (ref "C11") (pin "2") (pinfunction "2_2") (pintype "passive"))
      (node (ref "C12") (pin "2") (pinfunction "2_2") (pintype "passive"))
      (node (ref "C17") (pin "-") (pinfunction "-_-") (pintype "passive"))
      (node (ref "C18") (pin "2") (pinfunction "2_2") (pintype "passive"))
      (node (ref "C21") (pin "2") (pinfunction "2_2") (pintype "passive"))
      (node (ref "C24") (pin "-") (pinfunction "-_-") (pintype "passive"))
      (node (ref "C25") (pin "2") (pinfunction "2_2") (pintype "passive"))
      (node (ref "C31") (pin "2") (pinfunction "2_2") (pintype "passive"))
      (node (ref "C32") (pin "2") (pinfunction "2_2") (pintype "passive"))
      (node (ref "C4") (pin "1") (pinfunction "1_1") (pintype "passive"))
      (node (ref "C6") (pin "1") (pinfunction "1_1") (pintype "passive"))
      (node (ref "C8") (pin "2") (pinfunction "2_2") (pintype "passive"))
      (node (ref "IC1") (pin "8") (pinfunction "GND_8") (pintype "power_in"))
      (node (ref "IC2") (pin "2") (pinfunction "GND_2") (pintype "passive"))
      (node (ref "IC4") (pin "3") (pinfunction "A_3") (pintype "passive"))
      (node (ref "JP1") (pin "NO") (pinfunction "NO_NO") (pintype "passive"))
      (node (ref "JP5") (pin "1") (pinfunction "1_1") (pintype "passive"))
      (node (ref "Q3") (pin "2") (pinfunction "S_2") (pintype "passive"))
      (node (ref "Q4") (pin "2") (pinfunction "S_2") (pintype "passive"))
      (node (ref "Q5") (pin "1") (pinfunction "S_1") (pintype "passive"))
      (node (ref "Q5") (pin "2") (pinfunction "S_2") (pintype "passive"))
      (node (ref "Q5") (pin "3") (pinfunction "S_3") (pintype "passive"))
      (node (ref "Q6") (pin "2") (pinfunction "S_2") (pintype "passive"))
      (node (ref "R10") (pin "1") (pinfunction "1_1") (pintype "passive"))
      (node (ref "R27") (pin "2") (pinfunction "2_2") (pintype "passive"))
      (node (ref "R42") (pin "1") (pinfunction "1_1") (pintype "passive"))
      (node (ref "R5") (pin "1") (pinfunction "1_1") (pintype "passive"))
      (node (ref "TP2") (pin "1") (pinfunction "P$1_1") (pintype "bidirectional"))
      (node (ref "TR1") (pin "9") (pinfunction "S_COMM_9") (pintype "passive"))
      (node (ref "X3") (pin "7") (pinfunction "1_7") (pintype "passive"))
      (node (ref "X3") (pin "8") (pinfunction "1_8") (pintype "passive"))
      (node (ref "X3") (pin "9") (pinfunction "1_9") (pintype "passive"))
      (node (ref "ZD3") (pin "A") (pinfunction "A_A") (pintype "passive"))
      (node (ref "ZD4") (pin "A") (pinfunction "A_A") (pintype "passive"))
    )
    (net (code "17") (name "NFAULT") (class "Default")
      (node (ref "IC1") (pin "13") (pinfunction "~{ALERT}_13") (pintype "output"))
      (node (ref "X3") (pin "15") (pinfunction "1_15") (pintype "passive"))
    )
    (net (code "18") (name "Net-(C2-Pad2)") (class "Default")
      (node (ref "C2") (pin "2") (pinfunction "2_2") (pintype "passive"))
      (node (ref "R8") (pin "2") (pinfunction "2_2") (pintype "passive"))
      (node (ref "R9") (pin "2") (pinfunction "2_2") (pintype "passive"))
    )
    (net (code "19") (name "Net-(C13-Pad2)") (class "Default")
      (node (ref "C13") (pin "2") (pinfunction "2_2") (pintype "passive"))
      (node (ref "D2") (pin "C") (pinfunction "C_C") (pintype "passive"))
      (node (ref "R24") (pin "1") (pinfunction "1_1") (pintype "passive"))
    )
    (net (code "20") (name "Net-(C16-Pad1)") (class "Default")
      (node (ref "C16") (pin "1") (pinfunction "1_1") (pintype "passive"))
      (node (ref "R25") (pin "2") (pinfunction "2_2") (pintype "passive"))
    )
    (net (code "21") (name "Net-(C17-Pad+)") (class "Default")
      (node (ref "C17") (pin "+") (pinfunction "+_+") (pintype "passive"))
      (node (ref "D1") (pin "C") (pinfunction "C_C") (pintype "passive"))
      (node (ref "JP4") (pin "NO") (pinfunction "NO_NO") (pintype "passive"))
      (node (ref "L2") (pin "1") (pinfunction "1_1") (pintype "passive"))
      (node (ref "R25") (pin "1") (pinfunction "1_1") (pintype "passive"))
      (node (ref "R27") (pin "1") (pinfunction "1_1") (pintype "passive"))
    )
    (net (code "22") (name "Net-(C19-Pad1)") (class "Default")
      (node (ref "C19") (pin "1") (pinfunction "1_1") (pintype "passive"))
      (node (ref "R30") (pin "2") (pinfunction "2_2") (pintype "passive"))
    )
    (net (code "23") (name "Net-(C21-Pad1)") (class "Default")
      (node (ref "C21") (pin "1") (pinfunction "1_1") (pintype "passive"))
      (node (ref "JP3") (pin "COM") (pinfunction "COM_COM") (pintype "passive"))
    )
    (net (code "24") (name "Net-(C23-Pad1)") (class "Default")
      (node (ref "C23") (pin "1") (pinfunction "1_1") (pintype "passive"))
      (node (ref "R31") (pin "2") (pinfunction "2_2") (pintype "passive"))
    )
    (net (code "25") (name "Net-(C24-Pad+)") (class "Default")
      (node (ref "C24") (pin "+") (pinfunction "+_+") (pintype "passive"))
      (node (ref "D4") (pin "C") (pinfunction "C_C") (pintype "passive"))
      (node (ref "JP4") (pin "NC") (pinfunction "NC_NC") (pintype "passive"))
      (node (ref "L3") (pin "1") (pinfunction "1_1") (pintype "passive"))
      (node (ref "R31") (pin "1") (pinfunction "1_1") (pintype "passive"))
    )
    (net (code "26") (name "Net-(C26-Pad1)") (class "Default")
      (node (ref "C26") (pin "1") (pinfunction "1_1") (pintype "passive"))
      (node (ref "C29") (pin "2") (pinfunction "2_2") (pintype "passive"))
      (node (ref "R39") (pin "1") (pinfunction "1_1") (pintype "passive"))
    )
    (net (code "27") (name "Net-(C27-Pad1)") (class "Default")
      (node (ref "C27") (pin "1") (pinfunction "1_1") (pintype "passive"))
      (node (ref "R41") (pin "1") (pinfunction "1_1") (pintype "passive"))
    )
    (net (code "28") (name "Net-(D3-PadC)") (class "Default")
      (node (ref "D3") (pin "C") (pinfunction "C_C") (pintype "passive"))
      (node (ref "R28") (pin "1") (pinfunction "1_1") (pintype "passive"))
      (node (ref "R30") (pin "1") (pinfunction "1_1") (pintype "passive"))
    )
    (net (code "29") (name "Net-(D5-PadC)") (class "Default")
      (node (ref "D5") (pin "C") (pinfunction "C_C") (pintype "passive"))
      (node (ref "D6") (pin "C") (pinfunction "C_C") (pintype "passive"))
      (node (ref "R36") (pin "2") (pinfunction "2_2") (pintype "passive"))
    )
    (net (code "30") (name "Net-(IC1-A0)") (class "Default")
      (node (ref "IC1") (pin "3") (pinfunction "A0_3") (pintype "input"))
      (node (ref "JP1") (pin "COM") (pinfunction "COM_COM") (pintype "passive"))
    )
    (net (code "31") (name "Net-(IC1-TACH1)") (class "Default")
      (node (ref "C8") (pin "1") (pinfunction "1_1") (pintype "passive"))
      (node (ref "IC1") (pin "7") (pinfunction "TACH1_7") (pintype "input"))
      (node (ref "R17") (pin "1") (pinfunction "1_1") (pintype "passive"))
    )
    (net (code "32") (name "Net-(IC1-TACH2)") (class "Default")
      (node (ref "C10") (pin "1") (pinfunction "1_1") (pintype "passive"))
      (node (ref "IC1") (pin "9") (pinfunction "TACH2_9") (pintype "input"))
      (node (ref "R21") (pin "1") (pinfunction "1_1") (pintype "passive"))
    )
    (net (code "33") (name "Net-(IC1-~{FF}{slash}~{FS})") (class "Default")
      (node (ref "IC1") (pin "12") (pinfunction "~{FF}/~{FS}_12") (pintype "bidirectional"))
      (node (ref "R20") (pin "1") (pinfunction "1_1") (pintype "passive"))
    )
    (net (code "34") (name "Net-(IC1-~{SHDN})") (class "Default")
      (node (ref "IC1") (pin "11") (pinfunction "~{SHDN}_11") (pintype "output"))
      (node (ref "R19") (pin "1") (pinfunction "1_1") (pintype "passive"))
    )
    (net (code "35") (name "Net-(IC2-OUT)") (class "Default")
      (node (ref "C12") (pin "1") (pinfunction "1_1") (pintype "passive"))
      (node (ref "IC2") (pin "5") (pinfunction "OUT_5") (pintype "passive"))
      (node (ref "JP2") (pin "NO") (pinfunction "NO_NO") (pintype "passive"))
    )
    (net (code "36") (name "Net-(IC3-BR)") (class "Default")
      (node (ref "IC3") (pin "8") (pinfunction "BR_8") (pintype "input"))
      (node (ref "R29") (pin "2") (pinfunction "2_2") (pintype "passive"))
      (node (ref "R38") (pin "1") (pinfunction "1_1") (pintype "passive"))
    )
    (net (code "37") (name "Net-(IC3-FB)") (class "Default")
      (node (ref "C27") (pin "2") (pinfunction "2_2") (pintype "passive"))
      (node (ref "C30") (pin "1") (pinfunction "1_1") (pintype "passive"))
      (node (ref "IC3") (pin "7") (pinfunction "FB_7") (pintype "input"))
      (node (ref "OK3") (pin "4") (pinfunction "COL_4") (pintype "passive"))
    )
    (net (code "38") (name "Net-(IC3-ZCD)") (class "Default")
      (node (ref "C28") (pin "1") (pinfunction "1_1") (pintype "passive"))
      (node (ref "IC3") (pin "6") (pinfunction "ZCD_6") (pintype "input"))
      (node (ref "R34") (pin "1") (pinfunction "1_1") (pintype "passive"))
      (node (ref "R36") (pin "1") (pinfunction "1_1") (pintype "passive"))
      (node (ref "R40") (pin "2") (pinfunction "2_2") (pintype "passive"))
    )
    (net (code "39") (name "Net-(IC4-C)") (class "Default")
      (node (ref "C29") (pin "1") (pinfunction "1_1") (pintype "passive"))
      (node (ref "IC4") (pin "1") (pinfunction "C_1") (pintype "passive"))
      (node (ref "OK3") (pin "2") (pinfunction "C_2") (pintype "passive"))
      (node (ref "R35") (pin "2") (pinfunction "2_2") (pintype "passive"))
    )
    (net (code "40") (name "Net-(IC4-REF)") (class "Default")
      (node (ref "C26") (pin "2") (pinfunction "2_2") (pintype "passive"))
      (node (ref "IC4") (pin "2") (pinfunction "REF_2") (pintype "passive"))
      (node (ref "R37") (pin "1") (pinfunction "1_1") (pintype "passive"))
      (node (ref "R39") (pin "2") (pinfunction "2_2") (pintype "passive"))
      (node (ref "R42") (pin "2") (pinfunction "2_2") (pintype "passive"))
    )
    (net (code "41") (name "Net-(JP4-PadCOM)") (class "Default")
      (node (ref "JP4") (pin "COM") (pinfunction "COM_COM") (pintype "passive"))
      (node (ref "R32") (pin "1") (pinfunction "1_1") (pintype "passive"))
    )
    (net (code "42") (name "Net-(L1-1)") (class "Default")
      (node (ref "B1") (pin "+") (pinfunction "+_+") (pintype "passive"))
      (node (ref "C14") (pin "+") (pinfunction "+_+") (pintype "passive"))
      (node (ref "L1") (pin "P$1") (pinfunction "1_P$1") (pintype "passive"))
    )
    (net (code "43") (name "Net-(L1-2)") (class "Default")
      (node (ref "C13") (pin "1") (pinfunction "1_1") (pintype "passive"))
      (node (ref "C15") (pin "+") (pinfunction "+_+") (pintype "passive"))
      (node (ref "L1") (pin "P$2") (pinfunction "2_P$2") (pintype "passive"))
      (node (ref "R22") (pin "1") (pinfunction "1_1") (pintype "passive"))
      (node (ref "R23") (pin "1") (pinfunction "1_1") (pintype "passive"))
      (node (ref "TR1") (pin "2") (pinfunction "P1_2") (pintype "passive"))
    )
    (net (code "44") (name "Net-(LED1-PadC)") (class "Default")
      (node (ref "LED1") (pin "C") (pinfunction "C_C") (pintype "passive"))
      (node (ref "R15") (pin "1") (pinfunction "1_1") (pintype "passive"))
    )
    (net (code "45") (name "Net-(NTC1-P$2)") (class "Default")
      (node (ref "NTC1") (pin "2") (pinfunction "P$2_2") (pintype "bidirectional"))
      (node (ref "Q1") (pin "A1") (pinfunction "A1_A1") (pintype "passive"))
      (node (ref "R1") (pin "1") (pinfunction "1_1") (pintype "passive"))
    )
    (net (code "46") (name "Net-(OK1-A1)") (class "Default")
      (node (ref "OK1") (pin "4") (pinfunction "A1_4") (pintype "passive"))
      (node (ref "R4") (pin "1") (pinfunction "1_1") (pintype "passive"))
    )
    (net (code "47") (name "Net-(OK1-A2)") (class "Default")
      (node (ref "OK1") (pin "6") (pinfunction "A2_6") (pintype "passive"))
      (node (ref "Q2") (pin "G") (pinfunction "G_G") (pintype "passive"))
      (node (ref "R3") (pin "1") (pinfunction "1_1") (pintype "passive"))
    )
    (net (code "48") (name "Net-(OK1-C)") (class "Default")
      (node (ref "OK1") (pin "2") (pinfunction "C_2") (pintype "passive"))
      (node (ref "R2") (pin "1") (pinfunction "1_1") (pintype "passive"))
    )
    (net (code "49") (name "Net-(OK2-A1)") (class "Default")
      (node (ref "OK2") (pin "4") (pinfunction "A1_4") (pintype "passive"))
      (node (ref "Q1") (pin "G") (pinfunction "G_G") (pintype "passive"))
      (node (ref "R1") (pin "2") (pinfunction "2_2") (pintype "passive"))
    )
    (net (code "50") (name "Net-(OK2-A2)") (class "Default")
      (node (ref "OK2") (pin "6") (pinfunction "A2_6") (pintype "passive"))
      (node (ref "R6") (pin "1") (pinfunction "1_1") (pintype "passive"))
    )
    (net (code "51") (name "Net-(OK2-C)") (class "Default")
      (node (ref "OK2") (pin "2") (pinfunction "C_2") (pintype "passive"))
      (node (ref "R7") (pin "1") (pinfunction "1_1") (pintype "passive"))
    )
    (net (code "52") (name "Net-(OK3-A)") (class "Default")
      (node (ref "OK3") (pin "1") (pinfunction "A_1") (pintype "passive"))
      (node (ref "R32") (pin "2") (pinfunction "2_2") (pintype "passive"))
      (node (ref "R35") (pin "1") (pinfunction "1_1") (pintype "passive"))
    )
    (net (code "53") (name "Net-(Q4-D)") (class "Default")
      (node (ref "Q4") (pin "3") (pinfunction "D_3") (pintype "passive"))
      (node (ref "R7") (pin "2") (pinfunction "2_2") (pintype "passive"))
    )
    (net (code "54") (name "Net-(Q5-D)") (class "Default")
      (node (ref "C7") (pin "1") (pinfunction "1_1") (pintype "passive"))
      (node (ref "Q5") (pin "MB") (pinfunction "D_MB") (pintype "passive"))
      (node (ref "R11") (pin "1") (pinfunction "1_1") (pintype "passive"))
    )
    (net (code "55") (name "Net-(Q5-G)") (class "Default")
      (node (ref "C7") (pin "2") (pinfunction "2_2") (pintype "passive"))
      (node (ref "Q5") (pin "4") (pinfunction "G_4") (pintype "passive"))
      (node (ref "R18") (pin "2") (pinfunction "2_2") (pintype "passive"))
    )
    (net (code "56") (name "Net-(Q6-D)") (class "Default")
      (node (ref "Q6") (pin "3") (pinfunction "D_3") (pintype "passive"))
      (node (ref "R15") (pin "2") (pinfunction "2_2") (pintype "passive"))
    )
    (net (code "57") (name "Net-(R22-Pad2)") (class "Default")
      (node (ref "R22") (pin "2") (pinfunction "2_2") (pintype "passive"))
      (node (ref "R24") (pin "2") (pinfunction "2_2") (pintype "passive"))
    )
    (net (code "58") (name "Net-(R23-Pad2)") (class "Default")
      (node (ref "R23") (pin "2") (pinfunction "2_2") (pintype "passive"))
      (node (ref "R26") (pin "1") (pinfunction "1_1") (pintype "passive"))
    )
    (net (code "59") (name "Net-(R26-Pad2)") (class "Default")
      (node (ref "R26") (pin "2") (pinfunction "2_2") (pintype "passive"))
      (node (ref "R29") (pin "1") (pinfunction "1_1") (pintype "passive"))
    )
    (net (code "60") (name "Net-(R33-Pad1)") (class "Default")
      (node (ref "R33") (pin "1") (pinfunction "1_1") (pintype "passive"))
      (node (ref "R37") (pin "2") (pinfunction "2_2") (pintype "passive"))
    )
    (net (code "61") (name "Net-(TR1-P1_DOT)") (class "Default")
      (node (ref "D2") (pin "A") (pinfunction "A_A") (pintype "passive"))
      (node (ref "IC3") (pin "13") (pinfunction "DRAIN_13") (pintype "output"))
      (node (ref "IC3") (pin "14") (pinfunction "DRAIN_14") (pintype "output"))
      (node (ref "IC3") (pin "15") (pinfunction "DRAIN_15") (pintype "output"))
      (node (ref "IC3") (pin "16") (pinfunction "DRAIN_16") (pintype "output"))
      (node (ref "TR1") (pin "4") (pinfunction "P1_DOT_4") (pintype "passive"))
    )
    (net (code "62") (name "Net-(VAR1-P$1)") (class "Default")
      (node (ref "SAR1") (pin "P$1") (pinfunction "P$1_P$1") (pintype "bidirectional"))
      (node (ref "VAR1") (pin "1") (pinfunction "P$1_1") (pintype "bidirectional"))
      (node (ref "VAR2") (pin "2") (pinfunction "P$2_2") (pintype "bidirectional"))
    )
    (net (code "63") (name "Net-(X3H-1)") (class "Default")
      (node (ref "JP2") (pin "NC") (pinfunction "NC_NC") (pintype "passive"))
      (node (ref "X3") (pin "16") (pinfunction "1_16") (pintype "passive"))
    )
    (net (code "64") (name "Net-(X3J-1)") (class "Default")
      (node (ref "C33") (pin "1") (pinfunction "1_1") (pintype "passive"))
      (node (ref "L4") (pin "2") (pinfunction "2_2") (pintype "passive"))
      (node (ref "X3") (pin "3") (pinfunction "1_3") (pintype "passive"))
      (node (ref "X3") (pin "4") (pinfunction "1_4") (pintype "passive"))
    )
    (net (code "65") (name "Net-(X3L-1)") (class "Default")
      (node (ref "C34") (pin "1") (pinfunction "1_1") (pintype "passive"))
      (node (ref "L5") (pin "2") (pinfunction "2_2") (pintype "passive"))
      (node (ref "X3") (pin "5") (pinfunction "1_5") (pintype "passive"))
      (node (ref "X3") (pin "6") (pinfunction "1_6") (pintype "passive"))
    )
    (net (code "66") (name "Net-(X4A-S)") (class "Default")
      (node (ref "C3") (pin "2") (pinfunction "2_2") (pintype "passive"))
      (node (ref "C5") (pin "2") (pinfunction "2_2") (pintype "passive"))
      (node (ref "JP5") (pin "2") (pinfunction "2_2") (pintype "passive"))
      (node (ref "R11") (pin "2") (pinfunction "2_2") (pintype "passive"))
      (node (ref "X4") (pin "1") (pinfunction "S_1") (pintype "passive"))
      (node (ref "X5") (pin "1") (pinfunction "S_1") (pintype "passive"))
    )
    (net (code "67") (name "PE") (class "Default")
      (node (ref "C33") (pin "2") (pinfunction "2_2") (pintype "passive"))
      (node (ref "C34") (pin "2") (pinfunction "2_2") (pintype "passive"))
      (node (ref "J1") (pin "PE") (pinfunction "PE_PE") (pintype "bidirectional"))
      (node (ref "J2") (pin "P$1") (pinfunction "P$1_P$1") (pintype "bidirectional"))
      (node (ref "J2") (pin "P$2") (pinfunction "P$1_P$2") (pintype "bidirectional"))
      (node (ref "J3") (pin "P$1") (pinfunction "P$1_P$1") (pintype "bidirectional"))
      (node (ref "J3") (pin "P$2") (pinfunction "P$1_P$2") (pintype "bidirectional"))
      (node (ref "J4") (pin "P$1") (pinfunction "P$1_P$1") (pintype "bidirectional"))
      (node (ref "J4") (pin "P$2") (pinfunction "P$1_P$2") (pintype "bidirectional"))
      (node (ref "J5") (pin "1") (pinfunction "1_1") (pintype "passive"))
      (node (ref "J5") (pin "NC1") (pinfunction "1_NC1") (pintype "passive"))
      (node (ref "J5") (pin "NC2") (pinfunction "1_NC2") (pintype "passive"))
      (node (ref "J5") (pin "NC3") (pinfunction "1_NC3") (pintype "passive"))
      (node (ref "J5") (pin "NC4") (pinfunction "1_NC4") (pintype "passive"))
      (node (ref "JP3") (pin "NO") (pinfunction "NO_NO") (pintype "passive"))
      (node (ref "SAR1") (pin "P$2") (pinfunction "P$2_P$2") (pintype "bidirectional"))
      (node (ref "SW1") (pin "PE1") (pinfunction "PE_PE1") (pintype "power_in"))
      (node (ref "SW1") (pin "PE2") (pinfunction "PE_PE2") (pintype "power_in"))
      (node (ref "X1") (pin "3") (pinfunction "1_3") (pintype "passive"))
      (node (ref "X1") (pin "6") (pinfunction "1_6") (pintype "passive"))
      (node (ref "X2") (pin "3") (pinfunction "1_3") (pintype "passive"))
      (node (ref "X3") (pin "1") (pinfunction "1_1") (pintype "passive"))
      (node (ref "X3") (pin "2") (pinfunction "1_2") (pintype "passive"))
      (node (ref "ZD1") (pin "C") (pinfunction "1_C") (pintype "passive"))
      (node (ref "ZD2") (pin "C") (pinfunction "1_C") (pintype "passive"))
    )
    (net (code "68") (name "PWM_OUT") (class "Default")
      (node (ref "IC1") (pin "6") (pinfunction "PWM_6") (pintype "output"))
      (node (ref "R14") (pin "2") (pinfunction "2_2") (pintype "passive"))
      (node (ref "R18") (pin "1") (pinfunction "1_1") (pintype "passive"))
      (node (ref "X4") (pin "4") (pinfunction "S_4") (pintype "passive"))
      (node (ref "X5") (pin "4") (pinfunction "S_4") (pintype "passive"))
    )
    (net (code "69") (name "PWR_DIRECT") (class "Default")
      (node (ref "Q3") (pin "1") (pinfunction "G_1") (pintype "passive"))
      (node (ref "R5") (pin "2") (pinfunction "2_2") (pintype "passive"))
      (node (ref "X3") (pin "12") (pinfunction "1_12") (pintype "passive"))
    )
    (net (code "70") (name "PWR_DIR_OUT") (class "Default")
      (node (ref "Q3") (pin "3") (pinfunction "D_3") (pintype "passive"))
      (node (ref "Q6") (pin "1") (pinfunction "G_1") (pintype "passive"))
      (node (ref "R16") (pin "2") (pinfunction "2_2") (pintype "passive"))
      (node (ref "R2") (pin "2") (pinfunction "2_2") (pintype "passive"))
    )
    (net (code "71") (name "PWR_SSTART") (class "Default")
      (node (ref "Q4") (pin "1") (pinfunction "G_1") (pintype "passive"))
      (node (ref "R10") (pin "2") (pinfunction "2_2") (pintype "passive"))
      (node (ref "X3") (pin "11") (pinfunction "1_11") (pintype "passive"))
    )
    (net (code "72") (name "SSCL") (class "Default")
      (node (ref "IC1") (pin "15") (pinfunction "SCL_15") (pintype "input"))
      (node (ref "X3") (pin "13") (pinfunction "1_13") (pintype "passive"))
    )
    (net (code "73") (name "SSDA") (class "Default")
      (node (ref "IC1") (pin "14") (pinfunction "SDA_14") (pintype "bidirectional"))
      (node (ref "X3") (pin "14") (pinfunction "1_14") (pintype "passive"))
    )
    (net (code "74") (name "TEMP1_N") (class "Default")
      (node (ref "C9") (pin "2") (pinfunction "2_2") (pintype "passive"))
      (node (ref "IC1") (pin "2") (pinfunction "DXN_2") (pintype "bidirectional"))
      (node (ref "X6") (pin "2") (pinfunction "S_2") (pintype "passive"))
    )
    (net (code "75") (name "TEMP1_P") (class "Default")
      (node (ref "C9") (pin "1") (pinfunction "1_1") (pintype "passive"))
      (node (ref "IC1") (pin "1") (pinfunction "DXP_1") (pintype "input"))
      (node (ref "X6") (pin "1") (pinfunction "S_1") (pintype "passive"))
    )
    (net (code "76") (name "unconnected-(IC2-BYPASS-Pad4)") (class "Default")
      (node (ref "IC2") (pin "4") (pinfunction "BYPASS_4") (pintype "passive"))
    )
    (net (code "77") (name "unconnected-(KK1-K-PadA2,5)") (class "Default")
      (node (ref "KK1") (pin "A2,5") (pinfunction "K_A2,5") (pintype "passive"))
    )
    (net (code "78") (name "unconnected-(KK1-K-PadB2,5)") (class "Default")
      (node (ref "KK1") (pin "B2,5") (pinfunction "K_B2,5") (pintype "passive"))
    )
    (net (code "79") (name "unconnected-(TR1-P1_MIDDLE-Pad3)") (class "Default")
      (node (ref "TR1") (pin "3") (pinfunction "P1_MIDDLE_3") (pintype "passive"))
    )
  )
)
